# Copy_of_Connectors.net
KiCad netlist of a schematic drawn in Altium Designer
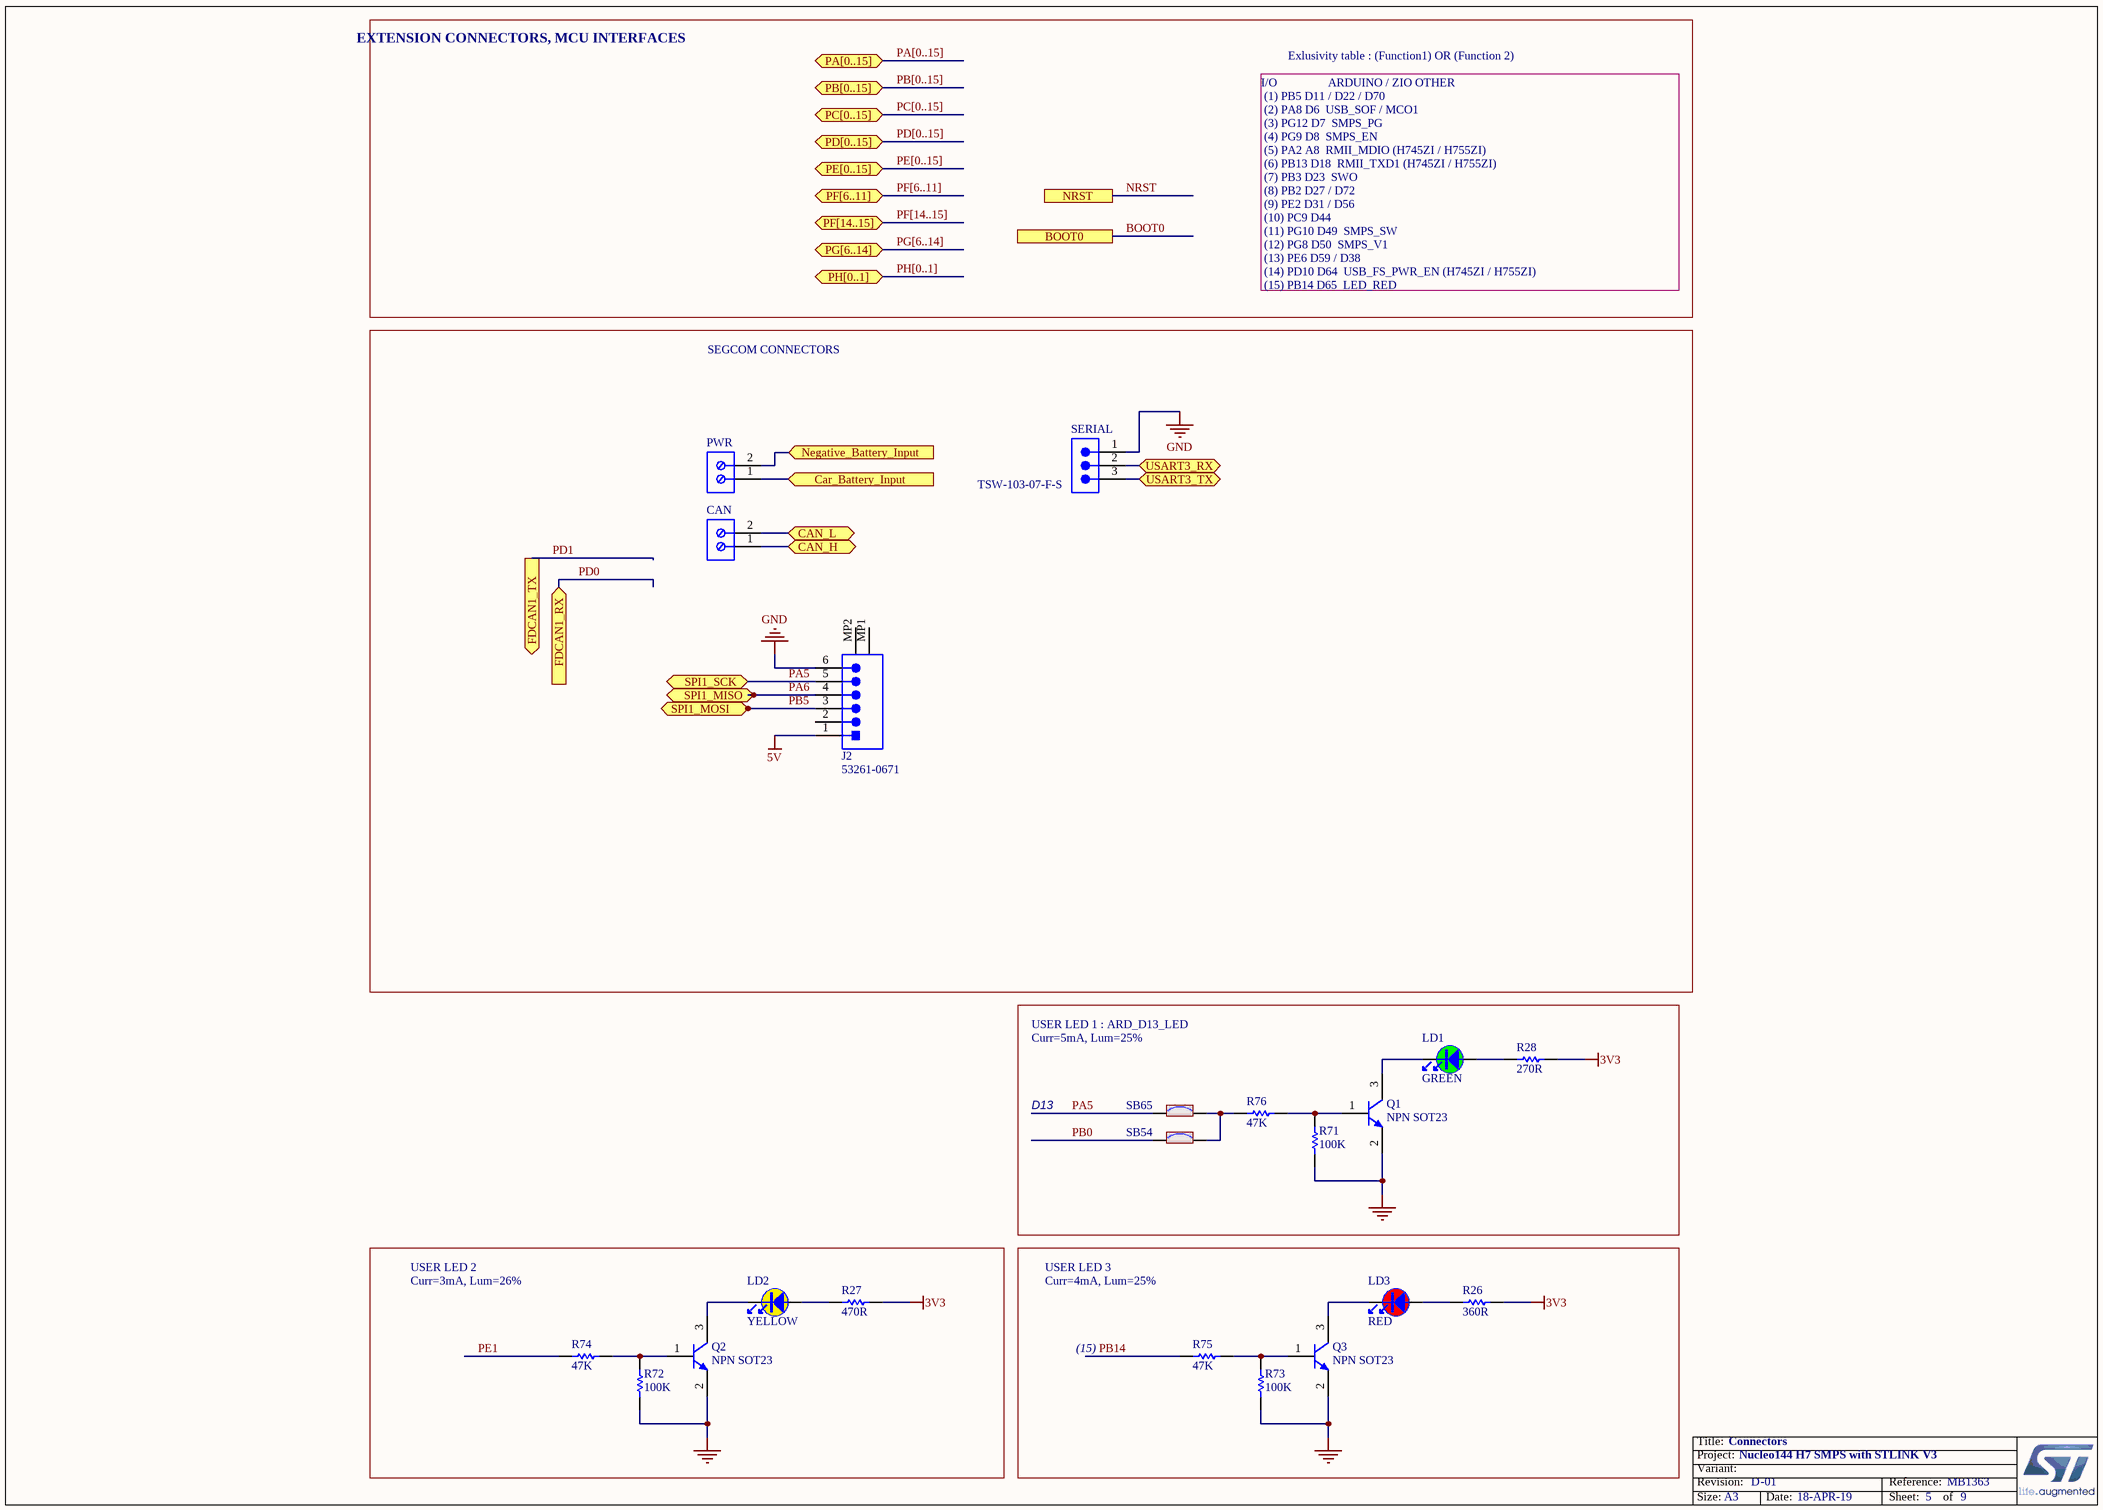
[diagram p0: Copy of Connectors.SchDoc]

(export (version "E")
  (design (tool "Eeschema 10.0.6"))
  (components
    (comp (ref "CAN")
      (value "~")
      (footprint "TECO-282836-2_V")
      (description "Female Header, Pitch 5 mm, 1 x 2 Position, Height 10 mm, Tail Length 3.5 mm, Rohs, Bulk")
      (fields (field (name "VOLTAGE") "300V") (field (name "MANUFACTURER") "TE Connectivity"))
      (libsource (lib "Altium Content Vault") (part "CN-1P-F-TB2"))
    )
    (comp (ref "J2")
      (value "53261-0671")
      (footprint "53261-0671")
      (description "1.25mm (.049\") Pitch PicoBlade Header, Surface Mount, Right Angle, Lead-free, 6 Circuits")
      (fields (field (name "MANUFACTURER") "Molex"))
      (libsource (lib "Antonio Vitor") (part "53261-0671"))
    )
    (comp (ref "LD1")
      (value "GREEN")
      (footprint "LED_0603_OSRAM_LG-Q396-PS-35_GREEN_1A2K_H0P4")
      (description "LED Green, 0603 SMD, Forward Voltage Typ=2V, Max=2.5V")
      (fields
        (field (name "INTERNAL_PART_NUMBER") "MCD-00588")
        (field (name "MANUFACTURER_PART_NUMBER") "LG Q396-PS-35")
        (field (name "PROVIDED_BY") "SUBCO")
      )
      (libsource (lib "MCD_PARTS_database") (part "LED_green"))
    )
    (comp (ref "LD2")
      (value "YELLOW")
      (footprint "LED_0603_OSRAM_LY-Q396-P1Q2-36_YELLOW_1A2K_H0P4")
      (description "LED Yellow, 0603 SMD, Forward Voltage min=1.7V, Typ=2V, Max=2.3V")
      (fields
        (field (name "INTERNAL_PART_NUMBER") "MCD-01061")
        (field (name "MANUFACTURER_PART_NUMBER") "LY Q396-P1Q2-36")
        (field (name "PROVIDED_BY") "SUBCO")
      )
      (libsource (lib "MCD_PARTS_database") (part "LED_yellow"))
    )
    (comp (ref "LD3")
      (value "RED")
      (footprint "LED_0603_OSRAM_LS-Q976-NR-1_RED_1A2K_H0P8")
      (description "LED Red, 0603 SMD, Forward Voltage Typ=2V, Max=2.5V")
      (fields
        (field (name "INTERNAL_PART_NUMBER") "MCD-00586")
        (field (name "MANUFACTURER_PART_NUMBER") "LS Q976-NR-1")
        (field (name "PROVIDED_BY") "SUBCO")
      )
      (libsource (lib "MCD_PARTS_database") (part "LED_red"))
    )
    (comp (ref "PWR")
      (value "~")
      (footprint "TECO-282836-2_V")
      (description "Female Header, Pitch 5 mm, 1 x 2 Position, Height 10 mm, Tail Length 3.5 mm, Rohs, Bulk")
      (fields (field (name "VOLTAGE") "300V") (field (name "MANUFACTURER") "TE Connectivity"))
      (libsource (lib "Altium Content Vault") (part "CN-1P-F-TB2"))
    )
    (comp (ref "Q1")
      (value "NPN SOT23")
      (footprint "NPN_SOT23")
      (description "NPN Bipolar Transistor")
      (fields
        (field (name "INTERNAL_PART_NUMBER") "MCD-00073")
        (field (name "MANUFACTURER_PART_NUMBER") "BSR14")
        (field (name "PROVIDED_BY") "SUBCO")
      )
      (libsource (lib "MCD_PARTS_database") (part "9013-SOT23"))
    )
    (comp (ref "Q2")
      (value "NPN SOT23")
      (footprint "NPN_SOT23")
      (description "NPN Bipolar Transistor")
      (fields
        (field (name "INTERNAL_PART_NUMBER") "MCD-00073")
        (field (name "MANUFACTURER_PART_NUMBER") "BSR14")
        (field (name "PROVIDED_BY") "SUBCO")
      )
      (libsource (lib "MCD_PARTS_database") (part "9013-SOT23"))
    )
    (comp (ref "Q3")
      (value "NPN SOT23")
      (footprint "NPN_SOT23")
      (description "NPN Bipolar Transistor")
      (fields
        (field (name "INTERNAL_PART_NUMBER") "MCD-00073")
        (field (name "MANUFACTURER_PART_NUMBER") "BSR14")
        (field (name "PROVIDED_BY") "SUBCO")
      )
      (libsource (lib "MCD_PARTS_database") (part "9013-SOT23"))
    )
    (comp (ref "R26")
      (value "360R")
      (footprint "R0603")
      (description "Resistor,360R,0603,1%,1/10W")
      (fields
        (field (name "INTERNAL_PART_NUMBER") "MCD-00462")
        (field (name "MANUFACTURER_PART_NUMBER") "RC0603FR-07360RL")
        (field (name "PROVIDED_BY") "SUBCO")
      )
      (libsource (lib "MCD_PARTS_database") (part "Resistor"))
    )
    (comp (ref "R27")
      (value "470R")
      (footprint "R0603")
      (description "Resistor,470R,0603,1%,1/10W")
      (fields
        (field (name "INTERNAL_PART_NUMBER") "MCD-00354")
        (field (name "MANUFACTURER_PART_NUMBER") "RC0603FR-07470RL")
        (field (name "PROVIDED_BY") "SUBCO")
      )
      (libsource (lib "MCD_PARTS_database") (part "Resistor"))
    )
    (comp (ref "R28")
      (value "270R")
      (footprint "R0402")
      (description "Resistor,270R,0402,1%,1/16W")
      (fields
        (field (name "INTERNAL_PART_NUMBER") "MCD-00441")
        (field (name "MANUFACTURER_PART_NUMBER") "RC0402FR-07270RL")
        (field (name "PROVIDED_BY") "SUBCO")
      )
      (libsource (lib "MCD_PARTS_database") (part "Resistor"))
    )
    (comp (ref "R71")
      (value "100K")
      (footprint "R0603")
      (description "Resistor,100K,0603,1%,1/10W")
      (fields
        (field (name "INTERNAL_PART_NUMBER") "MCD-00223")
        (field (name "MANUFACTURER_PART_NUMBER") "RC0603FR-07100KL")
        (field (name "PROVIDED_BY") "SUBCO")
      )
      (libsource (lib "MCD_PARTS_database") (part "Resistor"))
    )
    (comp (ref "R72")
      (value "100K")
      (footprint "R0603")
      (description "Resistor,100K,0603,1%,1/10W")
      (fields
        (field (name "INTERNAL_PART_NUMBER") "MCD-00223")
        (field (name "MANUFACTURER_PART_NUMBER") "RC0603FR-07100KL")
        (field (name "PROVIDED_BY") "SUBCO")
      )
      (libsource (lib "MCD_PARTS_database") (part "Resistor"))
    )
    (comp (ref "R73")
      (value "100K")
      (footprint "R0603")
      (description "Resistor,100K,0603,1%,1/10W")
      (fields
        (field (name "INTERNAL_PART_NUMBER") "MCD-00223")
        (field (name "MANUFACTURER_PART_NUMBER") "RC0603FR-07100KL")
        (field (name "PROVIDED_BY") "SUBCO")
      )
      (libsource (lib "MCD_PARTS_database") (part "Resistor"))
    )
    (comp (ref "R74")
      (value "47K")
      (footprint "R0603")
      (description "Resistor,47K,0603,1%,1/10W")
      (fields
        (field (name "INTERNAL_PART_NUMBER") "MCD-00222")
        (field (name "MANUFACTURER_PART_NUMBER") "RC0603FR-0747KL")
        (field (name "PROVIDED_BY") "SUBCO")
      )
      (libsource (lib "MCD_PARTS_database") (part "Resistor"))
    )
    (comp (ref "R75")
      (value "47K")
      (footprint "R0603")
      (description "Resistor,47K,0603,1%,1/10W")
      (fields
        (field (name "INTERNAL_PART_NUMBER") "MCD-00222")
        (field (name "MANUFACTURER_PART_NUMBER") "RC0603FR-0747KL")
        (field (name "PROVIDED_BY") "SUBCO")
      )
      (libsource (lib "MCD_PARTS_database") (part "Resistor"))
    )
    (comp (ref "R76")
      (value "47K")
      (footprint "R0603")
      (description "Resistor,47K,0603,1%,1/10W")
      (fields
        (field (name "INTERNAL_PART_NUMBER") "MCD-00222")
        (field (name "MANUFACTURER_PART_NUMBER") "RC0603FR-0747KL")
        (field (name "PROVIDED_BY") "SUBCO")
      )
      (libsource (lib "MCD_PARTS_database") (part "Resistor"))
    )
    (comp (ref "SB54")
      (value "SB_ON")
      (footprint "SOLDER-BRIDGE_R0603-0R")
      (description "Solder Bridge ON")
      (fields
        (field (name "INTERNAL_PART_NUMBER") "MCD-00071")
        (field (name "MANUFACTURER_PART_NUMBER") "RC0603JR-070RL")
        (field (name "PROVIDED_BY") "SUBCO")
      )
      (libsource (lib "MCD_PARTS_database") (part "SB_ON"))
    )
    (comp (ref "SB65")
      (value "SB_ON")
      (footprint "SOLDER-BRIDGE_R0603-0R")
      (description "Solder Bridge ON")
      (fields
        (field (name "INTERNAL_PART_NUMBER") "MCD-00071")
        (field (name "MANUFACTURER_PART_NUMBER") "RC0603JR-070RL")
        (field (name "PROVIDED_BY") "SUBCO")
      )
      (libsource (lib "MCD_PARTS_database") (part "SB_ON"))
    )
    (comp (ref "SERIAL")
      (value "TSW-103-07-F-S")
      (footprint "SMTC-TSW-103-07-X-S")
      (description "0.025\" SQ Post Header, Through-hole, Vertical, -55 to 125 degC, 2.54 mm Pitch, 3-Pin, Male, RoHS")
      (fields (field (name "MANUFACTURER") "Samtec"))
      (libsource (lib "Altium Content Vault") (part "SMTC-TSW-103-X-X-S-X"))
    )
  )
  (nets
    (net (code "93") (name "/CAN_H") (class "Default")
      (node (ref "CAN") (pin "1") (pinfunction "1_1") (pintype "passive"))
    )
    (net (code "94") (name "/CAN_L") (class "Default")
      (node (ref "CAN") (pin "2") (pinfunction "2_2") (pintype "passive"))
    )
    (net (code "95") (name "/Car_Battery_Input") (class "Default")
      (node (ref "PWR") (pin "1") (pinfunction "1_1") (pintype "passive"))
    )
    (net (code "97") (name "/Negative_Battery_Input") (class "Default")
      (node (ref "PWR") (pin "2") (pinfunction "2_2") (pintype "passive"))
    )
    (net (code "98") (name "/PA5") (class "Default")
      (node (ref "J2") (pin "5") (pinfunction "5_5") (pintype "passive"))
      (node (ref "SB65") (pin "1") (pinfunction "1_1") (pintype "passive"))
    )
    (net (code "99") (name "/PA6") (class "Default")
      (node (ref "J2") (pin "4") (pinfunction "4_4") (pintype "passive"))
    )
    (net (code "101") (name "/PB0") (class "Default")
      (node (ref "SB54") (pin "1") (pinfunction "1_1") (pintype "passive"))
    )
    (net (code "102") (name "/PB5") (class "Default")
      (node (ref "J2") (pin "3") (pinfunction "3_3") (pintype "passive"))
    )
    (net (code "103") (name "/PB14") (class "Default")
      (node (ref "R75") (pin "1") (pinfunction "1_1") (pintype "passive"))
    )
    (net (code "109") (name "/PE1") (class "Default")
      (node (ref "R74") (pin "1") (pinfunction "1_1") (pintype "passive"))
    )
    (net (code "115") (name "/USART3_RX") (class "Default")
      (node (ref "SERIAL") (pin "2") (pinfunction "2_2") (pintype "passive"))
    )
    (net (code "116") (name "/USART3_TX") (class "Default")
      (node (ref "SERIAL") (pin "3") (pinfunction "3_3") (pintype "passive"))
    )
    (net (code "117") (name "3V3") (class "Default")
      (node (ref "R26") (pin "2") (pinfunction "2_2") (pintype "passive"))
      (node (ref "R27") (pin "2") (pinfunction "2_2") (pintype "passive"))
      (node (ref "R28") (pin "2") (pinfunction "2_2") (pintype "passive"))
    )
    (net (code "118") (name "5V") (class "Default")
      (node (ref "J2") (pin "1") (pinfunction "1_1") (pintype "passive"))
    )
    (net (code "119") (name "GND") (class "Default")
      (node (ref "J2") (pin "6") (pinfunction "6_6") (pintype "passive"))
      (node (ref "Q1") (pin "2") (pinfunction "E_2") (pintype "passive"))
      (node (ref "Q2") (pin "2") (pinfunction "E_2") (pintype "passive"))
      (node (ref "Q3") (pin "2") (pinfunction "E_2") (pintype "passive"))
      (node (ref "R71") (pin "1") (pinfunction "1_1") (pintype "passive"))
      (node (ref "R72") (pin "1") (pinfunction "1_1") (pintype "passive"))
      (node (ref "R73") (pin "1") (pinfunction "1_1") (pintype "passive"))
      (node (ref "SERIAL") (pin "1") (pinfunction "1_1") (pintype "passive"))
    )
    (net (code "120") (name "Net-(LD1-Pad1)") (class "Default")
      (node (ref "LD1") (pin "1") (pintype "passive"))
      (node (ref "R28") (pin "1") (pinfunction "1_1") (pintype "passive"))
    )
    (net (code "121") (name "Net-(LD2-Pad1)") (class "Default")
      (node (ref "LD2") (pin "1") (pintype "passive"))
      (node (ref "R27") (pin "1") (pinfunction "1_1") (pintype "passive"))
    )
    (net (code "122") (name "Net-(LD3-Pad1)") (class "Default")
      (node (ref "LD3") (pin "1") (pintype "passive"))
      (node (ref "R26") (pin "1") (pinfunction "1_1") (pintype "passive"))
    )
    (net (code "123") (name "Net-(Q1-B)") (class "Default")
      (node (ref "Q1") (pin "1") (pinfunction "B_1") (pintype "passive"))
      (node (ref "R71") (pin "2") (pinfunction "2_2") (pintype "passive"))
      (node (ref "R76") (pin "2") (pinfunction "2_2") (pintype "passive"))
    )
    (net (code "124") (name "Net-(Q1-C)") (class "Default")
      (node (ref "LD1") (pin "2") (pintype "passive"))
      (node (ref "Q1") (pin "3") (pinfunction "C_3") (pintype "passive"))
    )
    (net (code "125") (name "Net-(Q2-B)") (class "Default")
      (node (ref "Q2") (pin "1") (pinfunction "B_1") (pintype "passive"))
      (node (ref "R72") (pin "2") (pinfunction "2_2") (pintype "passive"))
      (node (ref "R74") (pin "2") (pinfunction "2_2") (pintype "passive"))
    )
    (net (code "126") (name "Net-(Q2-C)") (class "Default")
      (node (ref "LD2") (pin "2") (pintype "passive"))
      (node (ref "Q2") (pin "3") (pinfunction "C_3") (pintype "passive"))
    )
    (net (code "127") (name "Net-(Q3-B)") (class "Default")
      (node (ref "Q3") (pin "1") (pinfunction "B_1") (pintype "passive"))
      (node (ref "R73") (pin "2") (pinfunction "2_2") (pintype "passive"))
      (node (ref "R75") (pin "2") (pinfunction "2_2") (pintype "passive"))
    )
    (net (code "128") (name "Net-(Q3-C)") (class "Default")
      (node (ref "LD3") (pin "2") (pintype "passive"))
      (node (ref "Q3") (pin "3") (pinfunction "C_3") (pintype "passive"))
    )
    (net (code "129") (name "Net-(R76-Pad1)") (class "Default")
      (node (ref "R76") (pin "1") (pinfunction "1_1") (pintype "passive"))
      (node (ref "SB54") (pin "2") (pinfunction "2_2") (pintype "passive"))
      (node (ref "SB65") (pin "2") (pinfunction "2_2") (pintype "passive"))
    )
    (net (code "130") (name "unconnected-(J2-Pad2)") (class "Default")
      (node (ref "J2") (pin "2") (pinfunction "2_2") (pintype "passive"))
    )
    (net (code "131") (name "unconnected-(J2-PadMP1)") (class "Default")
      (node (ref "J2") (pin "MP1") (pinfunction "MP1_MP1") (pintype "passive"))
    )
    (net (code "132") (name "unconnected-(J2-PadMP2)") (class "Default")
      (node (ref "J2") (pin "MP2") (pinfunction "MP2_MP2") (pintype "passive"))
    )
  )
)
